# sheet5.net
KiCad netlist of a schematic drawn in Altium Designer
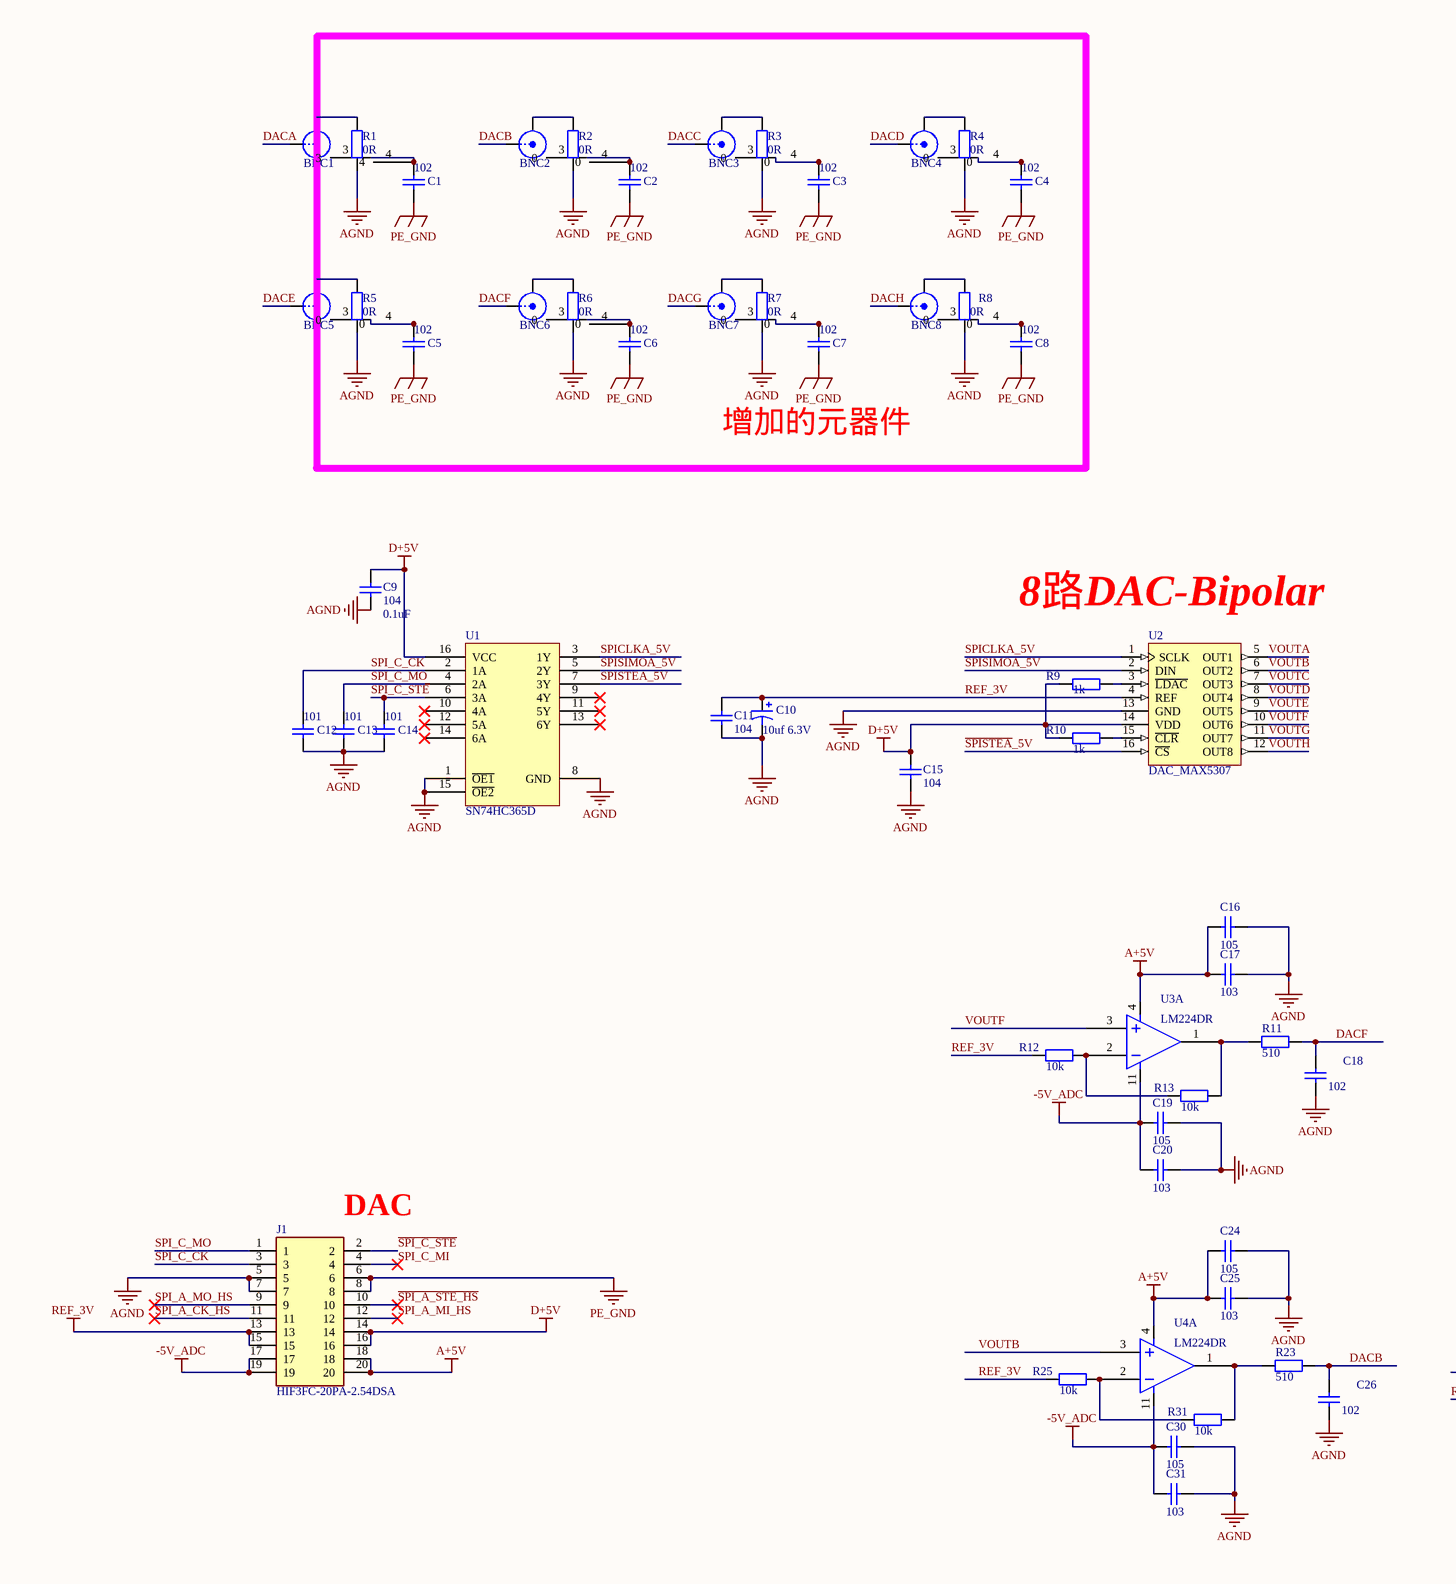
[diagram p0: sheet5.SchDoc, left]
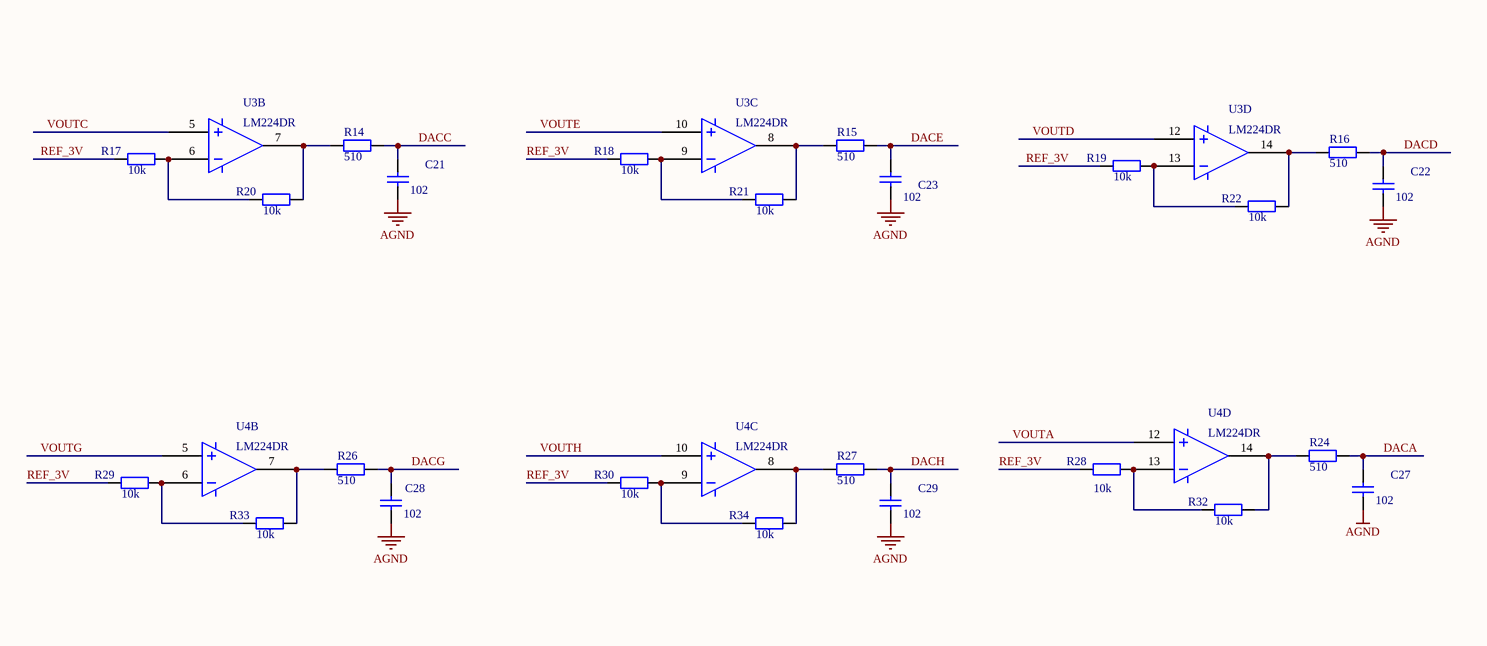
[diagram p1: sheet5.SchDoc, right]

(export (version "E")
  (design (tool "Eeschema 10.0.6"))
  (components
    (comp (ref "BNC1")
      (value "BNC")
      (footprint "BNC")
      (description "BNC Elbow Connector")
      (fields (field (name "PUBLISHER") "Altium Limited"))
      (libsource (lib "Miscellaneous Connectors") (part "BNC"))
    )
    (comp (ref "BNC2")
      (value "BNC")
      (footprint "BNC")
      (description "BNC Elbow Connector")
      (fields (field (name "PUBLISHER") "Altium Limited"))
      (libsource (lib "Miscellaneous Connectors") (part "BNC"))
    )
    (comp (ref "BNC3")
      (value "BNC")
      (footprint "BNC")
      (description "BNC Elbow Connector")
      (fields (field (name "PUBLISHER") "Altium Limited"))
      (libsource (lib "Miscellaneous Connectors") (part "BNC"))
    )
    (comp (ref "BNC4")
      (value "BNC")
      (footprint "BNC")
      (description "BNC Elbow Connector")
      (fields (field (name "PUBLISHER") "Altium Limited"))
      (libsource (lib "Miscellaneous Connectors") (part "BNC"))
    )
    (comp (ref "BNC5")
      (value "BNC")
      (footprint "BNC")
      (description "BNC Elbow Connector")
      (fields (field (name "PUBLISHER") "Altium Limited"))
      (libsource (lib "Miscellaneous Connectors") (part "BNC"))
    )
    (comp (ref "BNC6")
      (value "BNC")
      (footprint "BNC")
      (description "BNC Elbow Connector")
      (fields (field (name "PUBLISHER") "Altium Limited"))
      (libsource (lib "Miscellaneous Connectors") (part "BNC"))
    )
    (comp (ref "BNC7")
      (value "BNC")
      (footprint "BNC")
      (description "BNC Elbow Connector")
      (fields (field (name "PUBLISHER") "Altium Limited"))
      (libsource (lib "Miscellaneous Connectors") (part "BNC"))
    )
    (comp (ref "BNC8")
      (value "BNC")
      (footprint "BNC")
      (description "BNC Elbow Connector")
      (fields (field (name "PUBLISHER") "Altium Limited"))
      (libsource (lib "Miscellaneous Connectors") (part "BNC"))
    )
    (comp (ref "C1")
      (value "102")
      (footprint "0805")
      (description "Capacitor (Semiconductor SIM Model)")
      (fields (field (name "PUBLISHER") "Altium Limited"))
      (libsource (lib "Miscellaneous Devices") (part "Cap Semi"))
    )
    (comp (ref "C2")
      (value "102")
      (footprint "0805")
      (description "Capacitor (Semiconductor SIM Model)")
      (fields (field (name "PUBLISHER") "Altium Limited"))
      (libsource (lib "Miscellaneous Devices") (part "Cap Semi"))
    )
    (comp (ref "C3")
      (value "102")
      (footprint "0805")
      (description "Capacitor (Semiconductor SIM Model)")
      (fields (field (name "PUBLISHER") "Altium Limited"))
      (libsource (lib "Miscellaneous Devices") (part "Cap Semi"))
    )
    (comp (ref "C4")
      (value "102")
      (footprint "0805")
      (description "Capacitor (Semiconductor SIM Model)")
      (fields (field (name "PUBLISHER") "Altium Limited"))
      (libsource (lib "Miscellaneous Devices") (part "Cap Semi"))
    )
    (comp (ref "C5")
      (value "102")
      (footprint "0805")
      (description "Capacitor (Semiconductor SIM Model)")
      (fields (field (name "PUBLISHER") "Altium Limited"))
      (libsource (lib "Miscellaneous Devices") (part "Cap Semi"))
    )
    (comp (ref "C6")
      (value "102")
      (footprint "0805")
      (description "Capacitor (Semiconductor SIM Model)")
      (fields (field (name "PUBLISHER") "Altium Limited"))
      (libsource (lib "Miscellaneous Devices") (part "Cap Semi"))
    )
    (comp (ref "C7")
      (value "102")
      (footprint "0805")
      (description "Capacitor (Semiconductor SIM Model)")
      (fields (field (name "PUBLISHER") "Altium Limited"))
      (libsource (lib "Miscellaneous Devices") (part "Cap Semi"))
    )
    (comp (ref "C8")
      (value "102")
      (footprint "0805")
      (description "Capacitor (Semiconductor SIM Model)")
      (fields (field (name "PUBLISHER") "Altium Limited"))
      (libsource (lib "Miscellaneous Devices") (part "Cap Semi"))
    )
    (comp (ref "C9")
      (value "104")
      (footprint "0805")
      (description "Capacitor")
      (fields (field (name "ALTIUM_VALUE") "0.1uF") (field (name "PUBLISHER") "Altium Limited"))
      (libsource (lib "Miscellaneous Devices") (part "Cap"))
    )
    (comp (ref "C10")
      (value "10uf 6.3V")
      (footprint "1206 (钽电容)")
      (description "Polarized Capacitor (Radial)")
      (fields (field (name "PUBLISHER") "Altium Limited"))
      (libsource (lib "Miscellaneous Devices") (part "Cap Pol1"))
    )
    (comp (ref "C11")
      (value "104")
      (footprint "0805")
      (description "Capacitor")
      (fields (field (name "PUBLISHER") "Altium Limited"))
      (libsource (lib "Miscellaneous Devices") (part "Cap"))
    )
    (comp (ref "C12")
      (value "101")
      (footprint "0805")
      (description "Capacitor (Semiconductor SIM Model)")
      (fields (field (name "PUBLISHER") "Altium Limited"))
      (libsource (lib "Miscellaneous Devices") (part "Cap Semi"))
    )
    (comp (ref "C13")
      (value "101")
      (footprint "0805")
      (description "Capacitor (Semiconductor SIM Model)")
      (fields (field (name "PUBLISHER") "Altium Limited"))
      (libsource (lib "Miscellaneous Devices") (part "Cap Semi"))
    )
    (comp (ref "C14")
      (value "101")
      (footprint "0805")
      (description "Capacitor (Semiconductor SIM Model)")
      (fields (field (name "PUBLISHER") "Altium Limited"))
      (libsource (lib "Miscellaneous Devices") (part "Cap Semi"))
    )
    (comp (ref "C15")
      (value "104")
      (footprint "0805")
      (description "Capacitor")
      (fields (field (name "PUBLISHER") "Altium Limited"))
      (libsource (lib "Miscellaneous Devices") (part "Cap"))
    )
    (comp (ref "C16")
      (value "105")
      (footprint "0805")
      (description "Capacitor")
      (fields (field (name "PUBLISHER") "Altium Limited"))
      (libsource (lib "Miscellaneous Devices") (part "Cap"))
    )
    (comp (ref "C17")
      (value "103")
      (footprint "0805")
      (description "Capacitor")
      (fields (field (name "PUBLISHER") "Altium Limited"))
      (libsource (lib "Miscellaneous Devices") (part "Cap"))
    )
    (comp (ref "C18")
      (value "102")
      (footprint "0805")
      (description "Capacitor")
      (fields (field (name "PUBLISHER") "Altium Limited"))
      (libsource (lib "Miscellaneous Devices") (part "Cap"))
    )
    (comp (ref "C19")
      (value "105")
      (footprint "0805")
      (description "Capacitor")
      (fields (field (name "PUBLISHER") "Altium Limited"))
      (libsource (lib "Miscellaneous Devices") (part "Cap"))
    )
    (comp (ref "C20")
      (value "103")
      (footprint "0805")
      (description "Capacitor")
      (fields (field (name "PUBLISHER") "Altium Limited"))
      (libsource (lib "Miscellaneous Devices") (part "Cap"))
    )
    (comp (ref "C21")
      (value "102")
      (footprint "0805")
      (description "Capacitor")
      (fields (field (name "PUBLISHER") "Altium Limited"))
      (libsource (lib "Miscellaneous Devices") (part "Cap"))
    )
    (comp (ref "C22")
      (value "102")
      (footprint "0805")
      (description "Capacitor")
      (fields (field (name "PUBLISHER") "Altium Limited"))
      (libsource (lib "Miscellaneous Devices") (part "Cap"))
    )
    (comp (ref "C23")
      (value "102")
      (footprint "0805")
      (description "Capacitor")
      (fields (field (name "PUBLISHER") "Altium Limited"))
      (libsource (lib "Miscellaneous Devices") (part "Cap"))
    )
    (comp (ref "C24")
      (value "105")
      (footprint "0805")
      (description "Capacitor")
      (fields (field (name "PUBLISHER") "Altium Limited"))
      (libsource (lib "Miscellaneous Devices") (part "Cap"))
    )
    (comp (ref "C25")
      (value "103")
      (footprint "0805")
      (description "Capacitor")
      (fields (field (name "PUBLISHER") "Altium Limited"))
      (libsource (lib "Miscellaneous Devices") (part "Cap"))
    )
    (comp (ref "C26")
      (value "102")
      (footprint "0805")
      (description "Capacitor")
      (fields (field (name "PUBLISHER") "Altium Limited"))
      (libsource (lib "Miscellaneous Devices") (part "Cap"))
    )
    (comp (ref "C27")
      (value "102")
      (footprint "0805")
      (description "Capacitor")
      (fields (field (name "PUBLISHER") "Altium Limited"))
      (libsource (lib "Miscellaneous Devices") (part "Cap"))
    )
    (comp (ref "C28")
      (value "102")
      (footprint "0805")
      (description "Capacitor")
      (fields (field (name "PUBLISHER") "Altium Limited"))
      (libsource (lib "Miscellaneous Devices") (part "Cap"))
    )
    (comp (ref "C29")
      (value "102")
      (footprint "0805")
      (description "Capacitor")
      (fields (field (name "PUBLISHER") "Altium Limited"))
      (libsource (lib "Miscellaneous Devices") (part "Cap"))
    )
    (comp (ref "C30")
      (value "105")
      (footprint "0805")
      (description "Capacitor")
      (fields (field (name "PUBLISHER") "Altium Limited"))
      (libsource (lib "Miscellaneous Devices") (part "Cap"))
    )
    (comp (ref "C31")
      (value "103")
      (footprint "0805")
      (description "Capacitor")
      (fields (field (name "PUBLISHER") "Altium Limited"))
      (libsource (lib "Miscellaneous Devices") (part "Cap"))
    )
    (comp (ref "J1")
      (value "HIF3FC-20PA-2.54DSA")
      (footprint "SHDR20W56P254_2X10_3290X850X950P")
      (description "Connector")
      (fields
        (field (name "MANUFACTURER_PART_NUMBER") "HIF3FC-20PA-2.54DSA(71)")
        (field (name "MOUSER PART NUMBER") "798-HIF3FC20PA254D71")
      )
      (libsource (lib "Project_Arsene") (part "HIF3FC-20PA-2.54DSA"))
    )
    (comp (ref "R1")
      (value "0R")
      (footprint "0805")
      (description "Resistor")
      (fields (field (name "PUBLISHER") "Altium Limited"))
      (libsource (lib "") (part "Res2_1"))
    )
    (comp (ref "R2")
      (value "0R")
      (footprint "0805")
      (description "Resistor")
      (fields (field (name "PUBLISHER") "Altium Limited"))
      (libsource (lib "") (part "Res2_1"))
    )
    (comp (ref "R3")
      (value "0R")
      (footprint "0805")
      (description "Resistor")
      (fields (field (name "PUBLISHER") "Altium Limited"))
      (libsource (lib "") (part "Res2_1"))
    )
    (comp (ref "R4")
      (value "0R")
      (footprint "0805")
      (description "Resistor")
      (fields (field (name "PUBLISHER") "Altium Limited"))
      (libsource (lib "") (part "Res2_1"))
    )
    (comp (ref "R5")
      (value "0R")
      (footprint "0805")
      (description "Resistor")
      (fields (field (name "PUBLISHER") "Altium Limited"))
      (libsource (lib "") (part "Res2_1"))
    )
    (comp (ref "R6")
      (value "0R")
      (footprint "0805")
      (description "Resistor")
      (fields (field (name "PUBLISHER") "Altium Limited"))
      (libsource (lib "") (part "Res2_1"))
    )
    (comp (ref "R7")
      (value "0R")
      (footprint "0805")
      (description "Resistor")
      (fields (field (name "PUBLISHER") "Altium Limited"))
      (libsource (lib "") (part "Res2_1"))
    )
    (comp (ref "R8")
      (value "0R")
      (footprint "0805")
      (description "Resistor")
      (fields (field (name "PUBLISHER") "Altium Limited"))
      (libsource (lib "") (part "Res2_1"))
    )
    (comp (ref "R9")
      (value "1k")
      (footprint "0805")
      (description "Resistor")
      (fields (field (name "PUBLISHER") "Altium Limited"))
      (libsource (lib "Miscellaneous Devices") (part "Res2"))
    )
    (comp (ref "R10")
      (value "1k")
      (footprint "0805")
      (description "Resistor")
      (fields (field (name "PUBLISHER") "Altium Limited"))
      (libsource (lib "Miscellaneous Devices") (part "Res2"))
    )
    (comp (ref "R11")
      (value "510")
      (footprint "0805")
      (description "Resistor")
      (fields (field (name "PUBLISHER") "Altium Limited"))
      (libsource (lib "Miscellaneous Devices") (part "Res2"))
    )
    (comp (ref "R12")
      (value "10k")
      (footprint "0805")
      (description "Resistor")
      (fields (field (name "PUBLISHER") "Altium Limited"))
      (libsource (lib "Miscellaneous Devices") (part "Res2"))
    )
    (comp (ref "R13")
      (value "10k")
      (footprint "0805")
      (description "Resistor")
      (fields (field (name "PUBLISHER") "Altium Limited"))
      (libsource (lib "Miscellaneous Devices") (part "Res2"))
    )
    (comp (ref "R14")
      (value "510")
      (footprint "0805")
      (description "Resistor")
      (fields (field (name "PUBLISHER") "Altium Limited"))
      (libsource (lib "Miscellaneous Devices") (part "Res2"))
    )
    (comp (ref "R15")
      (value "510")
      (footprint "0805")
      (description "Resistor")
      (fields (field (name "PUBLISHER") "Altium Limited"))
      (libsource (lib "Miscellaneous Devices") (part "Res2"))
    )
    (comp (ref "R16")
      (value "510")
      (footprint "0805")
      (description "Resistor")
      (fields (field (name "PUBLISHER") "Altium Limited"))
      (libsource (lib "Miscellaneous Devices") (part "Res2"))
    )
    (comp (ref "R17")
      (value "10k")
      (footprint "0805")
      (description "Resistor")
      (fields (field (name "PUBLISHER") "Altium Limited"))
      (libsource (lib "Miscellaneous Devices") (part "Res2"))
    )
    (comp (ref "R18")
      (value "10k")
      (footprint "0805")
      (description "Resistor")
      (fields (field (name "PUBLISHER") "Altium Limited"))
      (libsource (lib "Miscellaneous Devices") (part "Res2"))
    )
    (comp (ref "R19")
      (value "10k")
      (footprint "0805")
      (description "Resistor")
      (fields (field (name "PUBLISHER") "Altium Limited"))
      (libsource (lib "Miscellaneous Devices") (part "Res2"))
    )
    (comp (ref "R20")
      (value "10k")
      (footprint "0805")
      (description "Resistor")
      (fields (field (name "PUBLISHER") "Altium Limited"))
      (libsource (lib "Miscellaneous Devices") (part "Res2"))
    )
    (comp (ref "R21")
      (value "10k")
      (footprint "0805")
      (description "Resistor")
      (fields (field (name "PUBLISHER") "Altium Limited"))
      (libsource (lib "Miscellaneous Devices") (part "Res2"))
    )
    (comp (ref "R22")
      (value "10k")
      (footprint "0805")
      (description "Resistor")
      (fields (field (name "PUBLISHER") "Altium Limited"))
      (libsource (lib "Miscellaneous Devices") (part "Res2"))
    )
    (comp (ref "R23")
      (value "510")
      (footprint "0805")
      (description "Resistor")
      (fields (field (name "PUBLISHER") "Altium Limited"))
      (libsource (lib "Miscellaneous Devices") (part "Res2"))
    )
    (comp (ref "R24")
      (value "510")
      (footprint "0805")
      (description "Resistor")
      (fields (field (name "PUBLISHER") "Altium Limited"))
      (libsource (lib "Miscellaneous Devices") (part "Res2"))
    )
    (comp (ref "R25")
      (value "10k")
      (footprint "0805")
      (description "Resistor")
      (fields (field (name "PUBLISHER") "Altium Limited"))
      (libsource (lib "Miscellaneous Devices") (part "Res2"))
    )
    (comp (ref "R26")
      (value "510")
      (footprint "0805")
      (description "Resistor")
      (fields (field (name "PUBLISHER") "Altium Limited"))
      (libsource (lib "Miscellaneous Devices") (part "Res2"))
    )
    (comp (ref "R27")
      (value "510")
      (footprint "0805")
      (description "Resistor")
      (fields (field (name "PUBLISHER") "Altium Limited"))
      (libsource (lib "Miscellaneous Devices") (part "Res2"))
    )
    (comp (ref "R28")
      (value "10k")
      (footprint "0805")
      (description "Resistor")
      (fields (field (name "PUBLISHER") "Altium Limited"))
      (libsource (lib "Miscellaneous Devices") (part "Res2"))
    )
    (comp (ref "R29")
      (value "10k")
      (footprint "0805")
      (description "Resistor")
      (fields (field (name "PUBLISHER") "Altium Limited"))
      (libsource (lib "Miscellaneous Devices") (part "Res2"))
    )
    (comp (ref "R30")
      (value "10k")
      (footprint "0805")
      (description "Resistor")
      (fields (field (name "PUBLISHER") "Altium Limited"))
      (libsource (lib "Miscellaneous Devices") (part "Res2"))
    )
    (comp (ref "R31")
      (value "10k")
      (footprint "0805")
      (description "Resistor")
      (fields (field (name "PUBLISHER") "Altium Limited"))
      (libsource (lib "Miscellaneous Devices") (part "Res2"))
    )
    (comp (ref "R32")
      (value "10k")
      (footprint "0805")
      (description "Resistor")
      (fields (field (name "PUBLISHER") "Altium Limited"))
      (libsource (lib "Miscellaneous Devices") (part "Res2"))
    )
    (comp (ref "R33")
      (value "10k")
      (footprint "0805")
      (description "Resistor")
      (fields (field (name "PUBLISHER") "Altium Limited"))
      (libsource (lib "Miscellaneous Devices") (part "Res2"))
    )
    (comp (ref "R34")
      (value "10k")
      (footprint "0805")
      (description "Resistor")
      (fields (field (name "PUBLISHER") "Altium Limited"))
      (libsource (lib "Miscellaneous Devices") (part "Res2"))
    )
    (comp (ref "U1") (value "SN74HC365D") (footprint "D016_N") (libsource (lib "总库") (part "SN74HC365D")))
    (comp (ref "U2")
      (value "DAC_MAX5307")
      (footprint "TSSOP16")
      (description "12-Bit DACs with Serial Interfece")
      (fields (field (name "PUBLISHER") "Altium Limited"))
      (libsource (lib "km") (part "MAX5307"))
    )
    (comp (ref "U3") (value "LM224DR") (footprint "SOIC14_M") (libsource (lib "C6000motor") (part "LM124")))
    (comp (ref "U4") (value "LM224DR") (footprint "SOIC14_M") (libsource (lib "C6000motor") (part "LM124")))
  )
  (nets
    (net (code "1") (name "-5V_ADC") (class "Default")
      (node (ref "C19") (pin "2") (pinfunction "2_2") (pintype "passive"))
      (node (ref "C20") (pin "1") (pinfunction "1_1") (pintype "passive"))
      (node (ref "C30") (pin "2") (pinfunction "2_2") (pintype "passive"))
      (node (ref "C31") (pin "1") (pinfunction "1_1") (pintype "passive"))
      (node (ref "J1") (pin "17") (pinfunction "17_17") (pintype "passive"))
      (node (ref "J1") (pin "19") (pinfunction "19_19") (pintype "passive"))
      (node (ref "U3") (pin "11") (pintype "passive"))
      (node (ref "U4") (pin "11") (pintype "passive"))
    )
    (net (code "2") (name "/DACA") (class "Default")
      (node (ref "BNC1") (pin "1") (pinfunction "1_1") (pintype "passive"))
      (node (ref "C27") (pin "1") (pinfunction "1_1") (pintype "passive"))
      (node (ref "R24") (pin "2") (pinfunction "2_2") (pintype "passive"))
    )
    (net (code "3") (name "/DACB") (class "Default")
      (node (ref "BNC2") (pin "1") (pinfunction "1_1") (pintype "passive"))
      (node (ref "C26") (pin "1") (pinfunction "1_1") (pintype "passive"))
      (node (ref "R23") (pin "2") (pinfunction "2_2") (pintype "passive"))
    )
    (net (code "4") (name "/DACC") (class "Default")
      (node (ref "BNC3") (pin "1") (pinfunction "1_1") (pintype "passive"))
      (node (ref "C21") (pin "1") (pinfunction "1_1") (pintype "passive"))
      (node (ref "R14") (pin "2") (pinfunction "2_2") (pintype "passive"))
    )
    (net (code "5") (name "/DACD") (class "Default")
      (node (ref "BNC4") (pin "1") (pinfunction "1_1") (pintype "passive"))
      (node (ref "C22") (pin "1") (pinfunction "1_1") (pintype "passive"))
      (node (ref "R16") (pin "2") (pinfunction "2_2") (pintype "passive"))
    )
    (net (code "6") (name "/DACE") (class "Default")
      (node (ref "BNC5") (pin "1") (pinfunction "1_1") (pintype "passive"))
      (node (ref "C23") (pin "1") (pinfunction "1_1") (pintype "passive"))
      (node (ref "R15") (pin "2") (pinfunction "2_2") (pintype "passive"))
    )
    (net (code "7") (name "/DACF") (class "Default")
      (node (ref "BNC6") (pin "1") (pinfunction "1_1") (pintype "passive"))
      (node (ref "C18") (pin "1") (pinfunction "1_1") (pintype "passive"))
      (node (ref "R11") (pin "2") (pinfunction "2_2") (pintype "passive"))
    )
    (net (code "8") (name "/DACG") (class "Default")
      (node (ref "BNC7") (pin "1") (pinfunction "1_1") (pintype "passive"))
      (node (ref "C28") (pin "1") (pinfunction "1_1") (pintype "passive"))
      (node (ref "R26") (pin "2") (pinfunction "2_2") (pintype "passive"))
    )
    (net (code "9") (name "/DACH") (class "Default")
      (node (ref "BNC8") (pin "1") (pinfunction "1_1") (pintype "passive"))
      (node (ref "C29") (pin "1") (pinfunction "1_1") (pintype "passive"))
      (node (ref "R27") (pin "2") (pinfunction "2_2") (pintype "passive"))
    )
    (net (code "10") (name "/SPICLKA_5V") (class "Default")
      (node (ref "U1") (pin "3") (pinfunction "1Y_3") (pintype "passive"))
      (node (ref "U2") (pin "1") (pinfunction "SCLK_1") (pintype "input"))
    )
    (net (code "11") (name "/SPISIMOA_5V") (class "Default")
      (node (ref "U1") (pin "5") (pinfunction "2Y_5") (pintype "passive"))
      (node (ref "U2") (pin "2") (pinfunction "DIN_2") (pintype "input"))
    )
    (net (code "12") (name "/SPI_A_CK_HS") (class "Default")
      (node (ref "J1") (pin "11") (pinfunction "11_11") (pintype "passive+no_connect"))
    )
    (net (code "13") (name "/SPI_A_MI_HS") (class "Default")
      (node (ref "J1") (pin "12") (pinfunction "12_12") (pintype "passive+no_connect"))
    )
    (net (code "14") (name "/SPI_A_MO_HS") (class "Default")
      (node (ref "J1") (pin "9") (pinfunction "9_9") (pintype "passive+no_connect"))
    )
    (net (code "15") (name "/SPI_C_CK") (class "Default")
      (node (ref "C12") (pin "1") (pinfunction "1_1") (pintype "passive"))
      (node (ref "J1") (pin "3") (pinfunction "3_3") (pintype "passive"))
      (node (ref "U1") (pin "2") (pinfunction "1A_2") (pintype "passive"))
    )
    (net (code "16") (name "/SPI_C_MI") (class "Default")
      (node (ref "J1") (pin "4") (pinfunction "4_4") (pintype "passive+no_connect"))
    )
    (net (code "17") (name "/SPI_C_MO") (class "Default")
      (node (ref "C13") (pin "1") (pinfunction "1_1") (pintype "passive"))
      (node (ref "J1") (pin "1") (pinfunction "1_1") (pintype "passive"))
      (node (ref "U1") (pin "4") (pinfunction "2A_4") (pintype "passive"))
    )
    (net (code "18") (name "/VOUTA") (class "Default")
      (node (ref "U2") (pin "5") (pinfunction "OUT1_5") (pintype "output"))
      (node (ref "U4") (pin "12") (pintype "passive"))
    )
    (net (code "19") (name "/VOUTB") (class "Default")
      (node (ref "U2") (pin "6") (pinfunction "OUT2_6") (pintype "output"))
      (node (ref "U4") (pin "3") (pintype "passive"))
    )
    (net (code "20") (name "/VOUTC") (class "Default")
      (node (ref "U2") (pin "7") (pinfunction "OUT3_7") (pintype "output"))
      (node (ref "U3") (pin "5") (pintype "passive"))
    )
    (net (code "21") (name "/VOUTD") (class "Default")
      (node (ref "U2") (pin "8") (pinfunction "OUT4_8") (pintype "output"))
      (node (ref "U3") (pin "12") (pintype "passive"))
    )
    (net (code "22") (name "/VOUTE") (class "Default")
      (node (ref "U2") (pin "9") (pinfunction "OUT5_9") (pintype "output"))
      (node (ref "U3") (pin "10") (pintype "passive"))
    )
    (net (code "23") (name "/VOUTF") (class "Default")
      (node (ref "U2") (pin "10") (pinfunction "OUT6_10") (pintype "output"))
      (node (ref "U3") (pin "3") (pintype "passive"))
    )
    (net (code "24") (name "/VOUTG") (class "Default")
      (node (ref "U2") (pin "11") (pinfunction "OUT7_11") (pintype "output"))
      (node (ref "U4") (pin "5") (pintype "passive"))
    )
    (net (code "25") (name "/VOUTH") (class "Default")
      (node (ref "U2") (pin "12") (pinfunction "OUT8_12") (pintype "output"))
      (node (ref "U4") (pin "10") (pintype "passive"))
    )
    (net (code "26") (name "/~{SPISTEA}_5V") (class "Default")
      (node (ref "U1") (pin "7") (pinfunction "3Y_7") (pintype "passive"))
      (node (ref "U2") (pin "16") (pinfunction "~{CS}_16") (pintype "input"))
    )
    (net (code "27") (name "/~{SPI_A_STE_HS}") (class "Default")
      (node (ref "J1") (pin "10") (pinfunction "10_10") (pintype "passive+no_connect"))
    )
    (net (code "28") (name "/~{SPI_C_STE}") (class "Default")
      (node (ref "C14") (pin "1") (pinfunction "1_1") (pintype "passive"))
      (node (ref "J1") (pin "2") (pinfunction "2_2") (pintype "passive"))
      (node (ref "U1") (pin "6") (pinfunction "3A_6") (pintype "passive"))
    )
    (net (code "29") (name "A+5V") (class "Default")
      (node (ref "C16") (pin "2") (pinfunction "2_2") (pintype "passive"))
      (node (ref "C17") (pin "1") (pinfunction "1_1") (pintype "passive"))
      (node (ref "C24") (pin "2") (pinfunction "2_2") (pintype "passive"))
      (node (ref "C25") (pin "1") (pinfunction "1_1") (pintype "passive"))
      (node (ref "J1") (pin "18") (pinfunction "18_18") (pintype "passive"))
      (node (ref "J1") (pin "20") (pinfunction "20_20") (pintype "passive"))
      (node (ref "U3") (pin "4") (pintype "passive"))
      (node (ref "U4") (pin "4") (pintype "passive"))
    )
    (net (code "30") (name "AGND") (class "Default")
      (node (ref "C10") (pin "2") (pinfunction "2_2") (pintype "passive"))
      (node (ref "C11") (pin "1") (pinfunction "1_1") (pintype "passive"))
      (node (ref "C12") (pin "2") (pinfunction "2_2") (pintype "passive"))
      (node (ref "C13") (pin "2") (pinfunction "2_2") (pintype "passive"))
      (node (ref "C14") (pin "2") (pinfunction "2_2") (pintype "passive"))
      (node (ref "C15") (pin "1") (pinfunction "1_1") (pintype "passive"))
      (node (ref "C16") (pin "1") (pinfunction "1_1") (pintype "passive"))
      (node (ref "C17") (pin "2") (pinfunction "2_2") (pintype "passive"))
      (node (ref "C18") (pin "2") (pinfunction "2_2") (pintype "passive"))
      (node (ref "C19") (pin "1") (pinfunction "1_1") (pintype "passive"))
      (node (ref "C20") (pin "2") (pinfunction "2_2") (pintype "passive"))
      (node (ref "C21") (pin "2") (pinfunction "2_2") (pintype "passive"))
      (node (ref "C22") (pin "2") (pinfunction "2_2") (pintype "passive"))
      (node (ref "C23") (pin "2") (pinfunction "2_2") (pintype "passive"))
      (node (ref "C24") (pin "1") (pinfunction "1_1") (pintype "passive"))
      (node (ref "C25") (pin "2") (pinfunction "2_2") (pintype "passive"))
      (node (ref "C26") (pin "2") (pinfunction "2_2") (pintype "passive"))
      (node (ref "C27") (pin "2") (pinfunction "2_2") (pintype "passive"))
      (node (ref "C28") (pin "2") (pinfunction "2_2") (pintype "passive"))
      (node (ref "C29") (pin "2") (pinfunction "2_2") (pintype "passive"))
      (node (ref "C30") (pin "1") (pinfunction "1_1") (pintype "passive"))
      (node (ref "C31") (pin "2") (pinfunction "2_2") (pintype "passive"))
      (node (ref "C9") (pin "2") (pinfunction "2_2") (pintype "passive"))
      (node (ref "J1") (pin "5") (pinfunction "5_5") (pintype "passive"))
      (node (ref "J1") (pin "7") (pinfunction "7_7") (pintype "passive"))
      (node (ref "R1") (pin "1") (pinfunction "1_1") (pintype "passive"))
      (node (ref "R2") (pin "1") (pinfunction "1_1") (pintype "passive"))
      (node (ref "R3") (pin "1") (pinfunction "1_1") (pintype "passive"))
      (node (ref "R4") (pin "1") (pinfunction "1_1") (pintype "passive"))
      (node (ref "R5") (pin "1") (pinfunction "1_1") (pintype "passive"))
      (node (ref "R6") (pin "1") (pinfunction "1_1") (pintype "passive"))
      (node (ref "R7") (pin "1") (pinfunction "1_1") (pintype "passive"))
      (node (ref "R8") (pin "1") (pinfunction "1_1") (pintype "passive"))
      (node (ref "U1") (pin "1") (pinfunction "~{OE1}_1") (pintype "passive"))
      (node (ref "U1") (pin "15") (pinfunction "~{OE2}_15") (pintype "passive"))
      (node (ref "U1") (pin "8") (pinfunction "GND_8") (pintype "passive"))
      (node (ref "U2") (pin "13") (pinfunction "GND_13") (pintype "power_in"))
    )
    (net (code "31") (name "D+5V") (class "Default")
      (node (ref "C15") (pin "2") (pinfunction "2_2") (pintype "passive"))
      (node (ref "C9") (pin "1") (pinfunction "1_1") (pintype "passive"))
      (node (ref "J1") (pin "14") (pinfunction "14_14") (pintype "passive"))
      (node (ref "J1") (pin "16") (pinfunction "16_16") (pintype "passive"))
      (node (ref "R10") (pin "1") (pinfunction "1_1") (pintype "passive"))
      (node (ref "R9") (pin "1") (pinfunction "1_1") (pintype "passive"))
      (node (ref "U1") (pin "16") (pinfunction "VCC_16") (pintype "passive"))
      (node (ref "U2") (pin "14") (pinfunction "VDD_14") (pintype "power_in"))
    )
    (net (code "32") (name "Net-(BNC1-Pad2)") (class "Default")
      (node (ref "BNC1") (pin "2") (pinfunction "2_2") (pintype "passive"))
      (node (ref "R1") (pin "2") (pinfunction "2_2") (pintype "passive"))
    )
    (net (code "33") (name "Net-(BNC1-Pad3)") (class "Default")
      (node (ref "BNC1") (pin "3") (pinfunction "3_3") (pintype "passive"))
      (node (ref "BNC1") (pin "4") (pinfunction "4_4") (pintype "passive"))
      (node (ref "C1") (pin "1") (pinfunction "1_1") (pintype "passive"))
    )
    (net (code "34") (name "Net-(BNC2-Pad2)") (class "Default")
      (node (ref "BNC2") (pin "2") (pinfunction "2_2") (pintype "passive"))
      (node (ref "R2") (pin "2") (pinfunction "2_2") (pintype "passive"))
    )
    (net (code "35") (name "Net-(BNC2-Pad3)") (class "Default")
      (node (ref "BNC2") (pin "3") (pinfunction "3_3") (pintype "passive"))
      (node (ref "BNC2") (pin "4") (pinfunction "4_4") (pintype "passive"))
      (node (ref "C2") (pin "1") (pinfunction "1_1") (pintype "passive"))
    )
    (net (code "36") (name "Net-(BNC3-Pad2)") (class "Default")
      (node (ref "BNC3") (pin "2") (pinfunction "2_2") (pintype "passive"))
      (node (ref "R3") (pin "2") (pinfunction "2_2") (pintype "passive"))
    )
    (net (code "37") (name "Net-(BNC3-Pad3)") (class "Default")
      (node (ref "BNC3") (pin "3") (pinfunction "3_3") (pintype "passive"))
      (node (ref "BNC3") (pin "4") (pinfunction "4_4") (pintype "passive"))
      (node (ref "C3") (pin "1") (pinfunction "1_1") (pintype "passive"))
    )
    (net (code "38") (name "Net-(BNC4-Pad2)") (class "Default")
      (node (ref "BNC4") (pin "2") (pinfunction "2_2") (pintype "passive"))
      (node (ref "R4") (pin "2") (pinfunction "2_2") (pintype "passive"))
    )
    (net (code "39") (name "Net-(BNC4-Pad3)") (class "Default")
      (node (ref "BNC4") (pin "3") (pinfunction "3_3") (pintype "passive"))
      (node (ref "BNC4") (pin "4") (pinfunction "4_4") (pintype "passive"))
      (node (ref "C4") (pin "1") (pinfunction "1_1") (pintype "passive"))
    )
    (net (code "40") (name "Net-(BNC5-Pad2)") (class "Default")
      (node (ref "BNC5") (pin "2") (pinfunction "2_2") (pintype "passive"))
      (node (ref "R5") (pin "2") (pinfunction "2_2") (pintype "passive"))
    )
    (net (code "41") (name "Net-(BNC5-Pad3)") (class "Default")
      (node (ref "BNC5") (pin "3") (pinfunction "3_3") (pintype "passive"))
      (node (ref "BNC5") (pin "4") (pinfunction "4_4") (pintype "passive"))
      (node (ref "C5") (pin "1") (pinfunction "1_1") (pintype "passive"))
    )
    (net (code "42") (name "Net-(BNC6-Pad2)") (class "Default")
      (node (ref "BNC6") (pin "2") (pinfunction "2_2") (pintype "passive"))
      (node (ref "R6") (pin "2") (pinfunction "2_2") (pintype "passive"))
    )
    (net (code "43") (name "Net-(BNC6-Pad3)") (class "Default")
      (node (ref "BNC6") (pin "3") (pinfunction "3_3") (pintype "passive"))
      (node (ref "BNC6") (pin "4") (pinfunction "4_4") (pintype "passive"))
      (node (ref "C6") (pin "1") (pinfunction "1_1") (pintype "passive"))
    )
    (net (code "44") (name "Net-(BNC7-Pad2)") (class "Default")
      (node (ref "BNC7") (pin "2") (pinfunction "2_2") (pintype "passive"))
      (node (ref "R7") (pin "2") (pinfunction "2_2") (pintype "passive"))
    )
    (net (code "45") (name "Net-(BNC7-Pad3)") (class "Default")
      (node (ref "BNC7") (pin "3") (pinfunction "3_3") (pintype "passive"))
      (node (ref "BNC7") (pin "4") (pinfunction "4_4") (pintype "passive"))
      (node (ref "C7") (pin "1") (pinfunction "1_1") (pintype "passive"))
    )
    (net (code "46") (name "Net-(BNC8-Pad2)") (class "Default")
      (node (ref "BNC8") (pin "2") (pinfunction "2_2") (pintype "passive"))
      (node (ref "R8") (pin "2") (pinfunction "2_2") (pintype "passive"))
    )
    (net (code "47") (name "Net-(BNC8-Pad3)") (class "Default")
      (node (ref "BNC8") (pin "3") (pinfunction "3_3") (pintype "passive"))
      (node (ref "BNC8") (pin "4") (pinfunction "4_4") (pintype "passive"))
      (node (ref "C8") (pin "1") (pinfunction "1_1") (pintype "passive"))
    )
    (net (code "48") (name "Net-(R11-Pad1)") (class "Default")
      (node (ref "R11") (pin "1") (pinfunction "1_1") (pintype "passive"))
      (node (ref "R13") (pin "2") (pinfunction "2_2") (pintype "passive"))
      (node (ref "U3") (pin "1") (pintype "passive"))
    )
    (net (code "49") (name "Net-(R12-Pad2)") (class "Default")
      (node (ref "R12") (pin "2") (pinfunction "2_2") (pintype "passive"))
      (node (ref "R13") (pin "1") (pinfunction "1_1") (pintype "passive"))
      (node (ref "U3") (pin "2") (pintype "passive"))
    )
    (net (code "50") (name "Net-(R14-Pad1)") (class "Default")
      (node (ref "R14") (pin "1") (pinfunction "1_1") (pintype "passive"))
      (node (ref "R20") (pin "2") (pinfunction "2_2") (pintype "passive"))
      (node (ref "U3") (pin "7") (pintype "passive"))
    )
    (net (code "51") (name "Net-(R15-Pad1)") (class "Default")
      (node (ref "R15") (pin "1") (pinfunction "1_1") (pintype "passive"))
      (node (ref "R21") (pin "2") (pinfunction "2_2") (pintype "passive"))
      (node (ref "U3") (pin "8") (pintype "passive"))
    )
    (net (code "52") (name "Net-(R16-Pad1)") (class "Default")
      (node (ref "R16") (pin "1") (pinfunction "1_1") (pintype "passive"))
      (node (ref "R22") (pin "2") (pinfunction "2_2") (pintype "passive"))
      (node (ref "U3") (pin "14") (pintype "passive"))
    )
    (net (code "53") (name "Net-(R17-Pad2)") (class "Default")
      (node (ref "R17") (pin "2") (pinfunction "2_2") (pintype "passive"))
      (node (ref "R20") (pin "1") (pinfunction "1_1") (pintype "passive"))
      (node (ref "U3") (pin "6") (pintype "passive"))
    )
    (net (code "54") (name "Net-(R18-Pad2)") (class "Default")
      (node (ref "R18") (pin "2") (pinfunction "2_2") (pintype "passive"))
      (node (ref "R21") (pin "1") (pinfunction "1_1") (pintype "passive"))
      (node (ref "U3") (pin "9") (pintype "passive"))
    )
    (net (code "55") (name "Net-(R19-Pad2)") (class "Default")
      (node (ref "R19") (pin "2") (pinfunction "2_2") (pintype "passive"))
      (node (ref "R22") (pin "1") (pinfunction "1_1") (pintype "passive"))
      (node (ref "U3") (pin "13") (pintype "passive"))
    )
    (net (code "56") (name "Net-(R23-Pad1)") (class "Default")
      (node (ref "R23") (pin "1") (pinfunction "1_1") (pintype "passive"))
      (node (ref "R31") (pin "2") (pinfunction "2_2") (pintype "passive"))
      (node (ref "U4") (pin "1") (pintype "passive"))
    )
    (net (code "57") (name "Net-(R24-Pad1)") (class "Default")
      (node (ref "R24") (pin "1") (pinfunction "1_1") (pintype "passive"))
      (node (ref "R32") (pin "2") (pinfunction "2_2") (pintype "passive"))
      (node (ref "U4") (pin "14") (pintype "passive"))
    )
    (net (code "58") (name "Net-(R25-Pad2)") (class "Default")
      (node (ref "R25") (pin "2") (pinfunction "2_2") (pintype "passive"))
      (node (ref "R31") (pin "1") (pinfunction "1_1") (pintype "passive"))
      (node (ref "U4") (pin "2") (pintype "passive"))
    )
    (net (code "59") (name "Net-(R26-Pad1)") (class "Default")
      (node (ref "R26") (pin "1") (pinfunction "1_1") (pintype "passive"))
      (node (ref "R33") (pin "2") (pinfunction "2_2") (pintype "passive"))
      (node (ref "U4") (pin "7") (pintype "passive"))
    )
    (net (code "60") (name "Net-(R27-Pad1)") (class "Default")
      (node (ref "R27") (pin "1") (pinfunction "1_1") (pintype "passive"))
      (node (ref "R34") (pin "2") (pinfunction "2_2") (pintype "passive"))
      (node (ref "U4") (pin "8") (pintype "passive"))
    )
    (net (code "61") (name "Net-(R28-Pad2)") (class "Default")
      (node (ref "R28") (pin "2") (pinfunction "2_2") (pintype "passive"))
      (node (ref "R32") (pin "1") (pinfunction "1_1") (pintype "passive"))
      (node (ref "U4") (pin "13") (pintype "passive"))
    )
    (net (code "62") (name "Net-(R29-Pad2)") (class "Default")
      (node (ref "R29") (pin "2") (pinfunction "2_2") (pintype "passive"))
      (node (ref "R33") (pin "1") (pinfunction "1_1") (pintype "passive"))
      (node (ref "U4") (pin "6") (pintype "passive"))
    )
    (net (code "63") (name "Net-(R30-Pad2)") (class "Default")
      (node (ref "R30") (pin "2") (pinfunction "2_2") (pintype "passive"))
      (node (ref "R34") (pin "1") (pinfunction "1_1") (pintype "passive"))
      (node (ref "U4") (pin "9") (pintype "passive"))
    )
    (net (code "64") (name "Net-(U2-~{CLR})") (class "Default")
      (node (ref "R10") (pin "2") (pinfunction "2_2") (pintype "passive"))
      (node (ref "U2") (pin "15") (pinfunction "~{CLR}_15") (pintype "input"))
    )
    (net (code "65") (name "Net-(U2-~{LDAC})") (class "Default")
      (node (ref "R9") (pin "2") (pinfunction "2_2") (pintype "passive"))
      (node (ref "U2") (pin "3") (pinfunction "~{LDAC}_3") (pintype "input"))
    )
    (net (code "66") (name "PE_GND") (class "Default")
      (node (ref "C1") (pin "2") (pinfunction "2_2") (pintype "passive"))
      (node (ref "C2") (pin "2") (pinfunction "2_2") (pintype "passive"))
      (node (ref "C3") (pin "2") (pinfunction "2_2") (pintype "passive"))
      (node (ref "C4") (pin "2") (pinfunction "2_2") (pintype "passive"))
      (node (ref "C5") (pin "2") (pinfunction "2_2") (pintype "passive"))
      (node (ref "C6") (pin "2") (pinfunction "2_2") (pintype "passive"))
      (node (ref "C7") (pin "2") (pinfunction "2_2") (pintype "passive"))
      (node (ref "C8") (pin "2") (pinfunction "2_2") (pintype "passive"))
      (node (ref "J1") (pin "6") (pinfunction "6_6") (pintype "passive"))
      (node (ref "J1") (pin "8") (pinfunction "8_8") (pintype "passive"))
    )
    (net (code "67") (name "REF_3V") (class "Default")
      (node (ref "C10") (pin "1") (pinfunction "1_1") (pintype "passive"))
      (node (ref "C11") (pin "2") (pinfunction "2_2") (pintype "passive"))
      (node (ref "J1") (pin "13") (pinfunction "13_13") (pintype "passive"))
      (node (ref "J1") (pin "15") (pinfunction "15_15") (pintype "passive"))
      (node (ref "R12") (pin "1") (pinfunction "1_1") (pintype "passive"))
      (node (ref "R17") (pin "1") (pinfunction "1_1") (pintype "passive"))
      (node (ref "R18") (pin "1") (pinfunction "1_1") (pintype "passive"))
      (node (ref "R19") (pin "1") (pinfunction "1_1") (pintype "passive"))
      (node (ref "R25") (pin "1") (pinfunction "1_1") (pintype "passive"))
      (node (ref "R28") (pin "1") (pinfunction "1_1") (pintype "passive"))
      (node (ref "R29") (pin "1") (pinfunction "1_1") (pintype "passive"))
      (node (ref "R30") (pin "1") (pinfunction "1_1") (pintype "passive"))
      (node (ref "U2") (pin "4") (pinfunction "REF_4") (pintype "input"))
    )
    (net (code "68") (name "unconnected-(U1-4A-Pad10)") (class "Default")
      (node (ref "U1") (pin "10") (pinfunction "4A_10") (pintype "passive+no_connect"))
    )
    (net (code "69") (name "unconnected-(U1-4Y-Pad9)") (class "Default")
      (node (ref "U1") (pin "9") (pinfunction "4Y_9") (pintype "passive+no_connect"))
    )
    (net (code "70") (name "unconnected-(U1-5A-Pad12)") (class "Default")
      (node (ref "U1") (pin "12") (pinfunction "5A_12") (pintype "passive+no_connect"))
    )
    (net (code "71") (name "unconnected-(U1-5Y-Pad11)") (class "Default")
      (node (ref "U1") (pin "11") (pinfunction "5Y_11") (pintype "passive+no_connect"))
    )
    (net (code "72") (name "unconnected-(U1-6A-Pad14)") (class "Default")
      (node (ref "U1") (pin "14") (pinfunction "6A_14") (pintype "passive+no_connect"))
    )
    (net (code "73") (name "unconnected-(U1-6Y-Pad13)") (class "Default")
      (node (ref "U1") (pin "13") (pinfunction "6Y_13") (pintype "passive+no_connect"))
    )
  )
)
